# SPACE_v2_2_WEMOS_D1R2.net
KiCad netlist of a schematic drawn in EAGLE
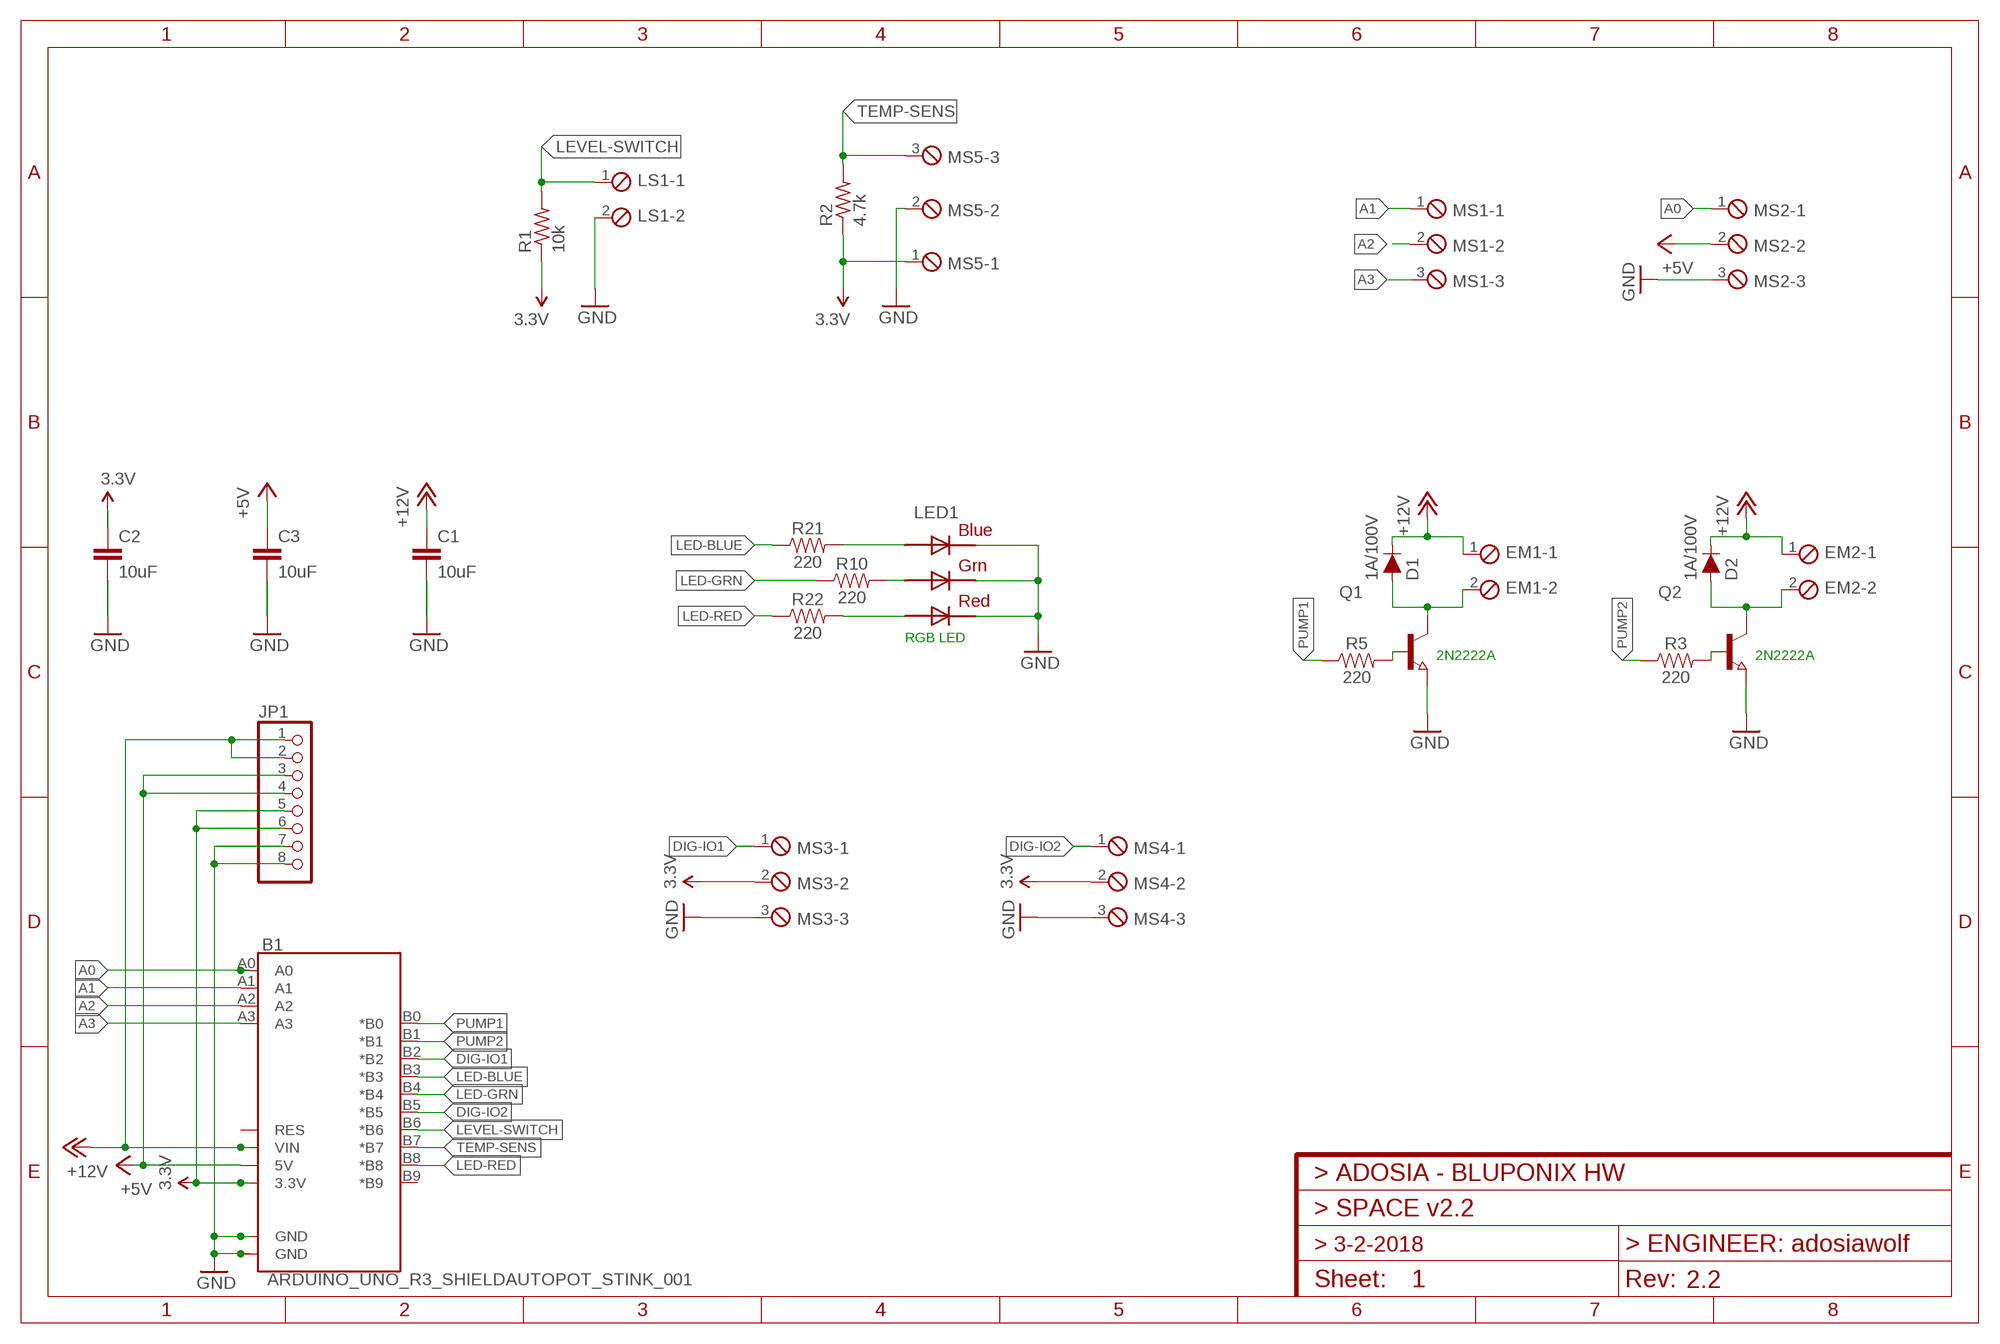
[diagram p0: schematic, sheet 1]

(export (version "E")
  (design (tool "Eeschema 10.0.6"))
  (components
    (comp (ref "B1")
      (value "ARDUINO_UNO_R3_SHIELDAUTOPOT_STINK_001")
      (footprint "eagle-import:UNO_R3_SHIELD_LOCK")
      (libsource (lib "eagle-import") (part "ARDUINO_UNO_R3_SHIELDAUTOPOT_STINK_001"))
    )
    (comp (ref "C1")
      (value "10uF")
      (footprint "eagle-import:0603-CAP@1")
      (libsource (lib "eagle-import") (part "10UF-6.3V-20%(0603)"))
    )
    (comp (ref "C2")
      (value "10uF")
      (footprint "eagle-import:0603-CAP@1")
      (libsource (lib "eagle-import") (part "10UF-6.3V-20%(0603)"))
    )
    (comp (ref "C3")
      (value "10uF")
      (footprint "eagle-import:0603-CAP@1")
      (libsource (lib "eagle-import") (part "10UF-6.3V-20%(0603)"))
    )
    (comp (ref "D1")
      (value "1A/100V")
      (footprint "eagle-import:SOD-323")
      (libsource (lib "eagle-import") (part "DIODE-BAS16J"))
    )
    (comp (ref "D2")
      (value "1A/100V")
      (footprint "eagle-import:SOD-323")
      (libsource (lib "eagle-import") (part "DIODE-BAS16J"))
    )
    (comp (ref "EM1")
      (value "MPT2")
      (footprint "eagle-import:2POL254")
      (libsource (lib "eagle-import") (part "MPT2"))
    )
    (comp (ref "EM2")
      (value "MPT2")
      (footprint "eagle-import:2POL254")
      (libsource (lib "eagle-import") (part "MPT2"))
    )
    (comp (ref "JP1")
      (value "PINHD-1X8/90")
      (footprint "eagle-import:1X08_90")
      (libsource (lib "eagle-import") (part "PINHD-1X8/90"))
    )
    (comp (ref "LED1")
      (value "RGBLED5050")
      (footprint "eagle-import:RGBLED5050")
      (libsource (lib "eagle-import") (part "RGBLED5050"))
    )
    (comp (ref "LS1")
      (value "MPT2")
      (footprint "eagle-import:2POL254")
      (libsource (lib "eagle-import") (part "MPT2"))
    )
    (comp (ref "MS1")
      (value "MPT3")
      (footprint "eagle-import:3POL254")
      (libsource (lib "eagle-import") (part "MPT3"))
    )
    (comp (ref "MS2")
      (value "MPT3")
      (footprint "eagle-import:3POL254")
      (libsource (lib "eagle-import") (part "MPT3"))
    )
    (comp (ref "MS3")
      (value "MPT3")
      (footprint "eagle-import:3POL254")
      (libsource (lib "eagle-import") (part "MPT3"))
    )
    (comp (ref "MS4")
      (value "MPT3")
      (footprint "eagle-import:3POL254")
      (libsource (lib "eagle-import") (part "MPT3"))
    )
    (comp (ref "MS5")
      (value "MPT3")
      (footprint "eagle-import:3POL254")
      (libsource (lib "eagle-import") (part "MPT3"))
    )
    (comp (ref "Q1")
      (value "NPN-TRANSISTOR_SOT23")
      (footprint "eagle-import:SOT23")
      (libsource (lib "eagle-import") (part "NPN-TRANSISTOR_SOT23"))
    )
    (comp (ref "Q2")
      (value "NPN-TRANSISTOR_SOT23")
      (footprint "eagle-import:SOT23")
      (libsource (lib "eagle-import") (part "NPN-TRANSISTOR_SOT23"))
    )
    (comp (ref "R1")
      (value "10k")
      (footprint "eagle-import:M1206")
      (libsource (lib "eagle-import") (part "R-US_M1206"))
    )
    (comp (ref "R2")
      (value "4.7k")
      (footprint "eagle-import:M1206")
      (libsource (lib "eagle-import") (part "R-US_M1206"))
    )
    (comp (ref "R3")
      (value "220")
      (footprint "eagle-import:0603")
      (libsource (lib "eagle-import") (part "220OHM-0603-1/10W-1%"))
    )
    (comp (ref "R5")
      (value "220")
      (footprint "eagle-import:0603")
      (libsource (lib "eagle-import") (part "220OHM-0603-1/10W-1%"))
    )
    (comp (ref "R10")
      (value "220")
      (footprint "eagle-import:0603")
      (libsource (lib "eagle-import") (part "220OHM-0603-1/10W-1%"))
    )
    (comp (ref "R21")
      (value "220")
      (footprint "eagle-import:0603")
      (libsource (lib "eagle-import") (part "220OHM-0603-1/10W-1%"))
    )
    (comp (ref "R22")
      (value "220")
      (footprint "eagle-import:0603")
      (libsource (lib "eagle-import") (part "220OHM-0603-1/10W-1%"))
    )
  )
  (nets
    (net (code "1") (name "+5V") (class "Default")
      (node (ref "B1") (pin "5V") (pinfunction "5V_5V") (pintype "bidirectional"))
      (node (ref "C3") (pin "1") (pinfunction "1_1") (pintype "passive"))
      (node (ref "JP1") (pin "3") (pinfunction "3_3") (pintype "passive"))
      (node (ref "JP1") (pin "4") (pinfunction "4_4") (pintype "passive"))
      (node (ref "MS2") (pin "2") (pinfunction "1_2") (pintype "passive"))
    )
    (net (code "2") (name "+12V") (class "Default")
      (node (ref "B1") (pin "VIN") (pinfunction "VIN_VIN") (pintype "bidirectional"))
      (node (ref "C1") (pin "1") (pinfunction "1_1") (pintype "passive"))
      (node (ref "D1") (pin "C") (pinfunction "C_C") (pintype "passive"))
      (node (ref "D2") (pin "C") (pinfunction "C_C") (pintype "passive"))
      (node (ref "EM1") (pin "1") (pinfunction "1_1") (pintype "passive"))
      (node (ref "EM2") (pin "1") (pinfunction "1_1") (pintype "passive"))
      (node (ref "JP1") (pin "1") (pinfunction "1_1") (pintype "passive"))
      (node (ref "JP1") (pin "2") (pinfunction "2_2") (pintype "passive"))
    )
    (net (code "3") (name "3.3V") (class "Default")
      (node (ref "B1") (pin "3.3V") (pinfunction "3.3V_3.3V") (pintype "bidirectional"))
      (node (ref "C2") (pin "1") (pinfunction "1_1") (pintype "passive"))
      (node (ref "JP1") (pin "5") (pinfunction "5_5") (pintype "passive"))
      (node (ref "JP1") (pin "6") (pinfunction "6_6") (pintype "passive"))
      (node (ref "MS3") (pin "2") (pinfunction "1_2") (pintype "passive"))
      (node (ref "MS4") (pin "2") (pinfunction "1_2") (pintype "passive"))
      (node (ref "MS5") (pin "1") (pinfunction "1_1") (pintype "passive"))
      (node (ref "R1") (pin "1") (pinfunction "1_1") (pintype "passive"))
      (node (ref "R2") (pin "1") (pinfunction "1_1") (pintype "passive"))
    )
    (net (code "4") (name "A0") (class "Default")
      (node (ref "B1") (pin "A0") (pinfunction "A0_A0") (pintype "bidirectional"))
      (node (ref "MS2") (pin "1") (pinfunction "1_1") (pintype "passive"))
    )
    (net (code "5") (name "A1") (class "Default")
      (node (ref "B1") (pin "A1") (pinfunction "A1_A1") (pintype "bidirectional"))
      (node (ref "MS1") (pin "1") (pinfunction "1_1") (pintype "passive"))
    )
    (net (code "6") (name "A2") (class "Default")
      (node (ref "B1") (pin "A2") (pinfunction "A2_A2") (pintype "bidirectional"))
      (node (ref "MS1") (pin "2") (pinfunction "1_2") (pintype "passive"))
    )
    (net (code "7") (name "A3") (class "Default")
      (node (ref "B1") (pin "A3") (pinfunction "A3_A3") (pintype "bidirectional"))
      (node (ref "MS1") (pin "3") (pinfunction "1_3") (pintype "passive"))
    )
    (net (code "8") (name "DIG-IO1") (class "Default")
      (node (ref "B1") (pin "B2") (pinfunction "*B2_B2") (pintype "bidirectional"))
      (node (ref "MS3") (pin "1") (pinfunction "1_1") (pintype "passive"))
    )
    (net (code "9") (name "DIG-IO2") (class "Default")
      (node (ref "B1") (pin "B5") (pinfunction "*B5_B5") (pintype "bidirectional"))
      (node (ref "MS4") (pin "1") (pinfunction "1_1") (pintype "passive"))
    )
    (net (code "10") (name "GND") (class "Default")
      (node (ref "B1") (pin "GND@0") (pinfunction "GND_GND@0") (pintype "bidirectional"))
      (node (ref "B1") (pin "GND@1") (pinfunction "GND_GND@1") (pintype "bidirectional"))
      (node (ref "C1") (pin "2") (pinfunction "2_2") (pintype "passive"))
      (node (ref "C2") (pin "2") (pinfunction "2_2") (pintype "passive"))
      (node (ref "C3") (pin "2") (pinfunction "2_2") (pintype "passive"))
      (node (ref "JP1") (pin "7") (pinfunction "7_7") (pintype "passive"))
      (node (ref "JP1") (pin "8") (pinfunction "8_8") (pintype "passive"))
      (node (ref "LED1") (pin "4") (pinfunction "BLUE_C_4") (pintype "bidirectional"))
      (node (ref "LED1") (pin "5") (pinfunction "RED_C_5") (pintype "bidirectional"))
      (node (ref "LED1") (pin "6") (pinfunction "GREEN_C_6") (pintype "bidirectional"))
      (node (ref "LS1") (pin "2") (pinfunction "1_2") (pintype "passive"))
      (node (ref "MS2") (pin "3") (pinfunction "1_3") (pintype "passive"))
      (node (ref "MS3") (pin "3") (pinfunction "1_3") (pintype "passive"))
      (node (ref "MS4") (pin "3") (pinfunction "1_3") (pintype "passive"))
      (node (ref "MS5") (pin "2") (pinfunction "1_2") (pintype "passive"))
      (node (ref "Q1") (pin "2") (pinfunction "E_2") (pintype "passive"))
      (node (ref "Q2") (pin "2") (pinfunction "E_2") (pintype "passive"))
    )
    (net (code "11") (name "LED-BLUE") (class "Default")
      (node (ref "B1") (pin "B3") (pinfunction "*B3_B3") (pintype "bidirectional"))
      (node (ref "R21") (pin "1") (pinfunction "1_1") (pintype "passive"))
    )
    (net (code "12") (name "LED-GRN") (class "Default")
      (node (ref "B1") (pin "B4") (pinfunction "*B4_B4") (pintype "bidirectional"))
      (node (ref "R10") (pin "1") (pinfunction "1_1") (pintype "passive"))
    )
    (net (code "13") (name "LED-RED") (class "Default")
      (node (ref "B1") (pin "B8") (pinfunction "*B8_B8") (pintype "bidirectional"))
      (node (ref "R22") (pin "1") (pinfunction "1_1") (pintype "passive"))
    )
    (net (code "14") (name "LEVEL-SWITCH") (class "Default")
      (node (ref "B1") (pin "B6") (pinfunction "*B6_B6") (pintype "bidirectional"))
      (node (ref "LS1") (pin "1") (pinfunction "1_1") (pintype "passive"))
      (node (ref "R1") (pin "2") (pinfunction "2_2") (pintype "passive"))
    )
    (net (code "15") (name "Net-(EM1B-1)") (class "Default")
      (node (ref "D1") (pin "A") (pinfunction "A_A") (pintype "passive"))
      (node (ref "EM1") (pin "2") (pinfunction "1_2") (pintype "passive"))
      (node (ref "Q1") (pin "3") (pinfunction "C_3") (pintype "passive"))
    )
    (net (code "16") (name "Net-(EM2B-1)") (class "Default")
      (node (ref "D2") (pin "A") (pinfunction "A_A") (pintype "passive"))
      (node (ref "EM2") (pin "2") (pinfunction "1_2") (pintype "passive"))
      (node (ref "Q2") (pin "3") (pinfunction "C_3") (pintype "passive"))
    )
    (net (code "17") (name "Net-(LED1-BLUE_A)") (class "Default")
      (node (ref "LED1") (pin "3") (pinfunction "BLUE_A_3") (pintype "bidirectional"))
      (node (ref "R21") (pin "2") (pinfunction "2_2") (pintype "passive"))
    )
    (net (code "18") (name "Net-(LED1-GREEN_A)") (class "Default")
      (node (ref "LED1") (pin "1") (pinfunction "GREEN_A_1") (pintype "bidirectional"))
      (node (ref "R10") (pin "2") (pinfunction "2_2") (pintype "passive"))
    )
    (net (code "19") (name "Net-(LED1-RED_A)") (class "Default")
      (node (ref "LED1") (pin "2") (pinfunction "RED_A_2") (pintype "bidirectional"))
      (node (ref "R22") (pin "2") (pinfunction "2_2") (pintype "passive"))
    )
    (net (code "20") (name "Net-(Q1-B)") (class "Default")
      (node (ref "Q1") (pin "1") (pinfunction "B_1") (pintype "passive"))
      (node (ref "R5") (pin "2") (pinfunction "2_2") (pintype "passive"))
    )
    (net (code "21") (name "Net-(Q2-B)") (class "Default")
      (node (ref "Q2") (pin "1") (pinfunction "B_1") (pintype "passive"))
      (node (ref "R3") (pin "2") (pinfunction "2_2") (pintype "passive"))
    )
    (net (code "22") (name "PUMP1") (class "Default")
      (node (ref "B1") (pin "B0") (pinfunction "*B0_B0") (pintype "bidirectional"))
      (node (ref "R5") (pin "1") (pinfunction "1_1") (pintype "passive"))
    )
    (net (code "23") (name "PUMP2") (class "Default")
      (node (ref "B1") (pin "B1") (pinfunction "*B1_B1") (pintype "bidirectional"))
      (node (ref "R3") (pin "1") (pinfunction "1_1") (pintype "passive"))
    )
    (net (code "24") (name "TEMP-SENS") (class "Default")
      (node (ref "B1") (pin "B7") (pinfunction "*B7_B7") (pintype "bidirectional"))
      (node (ref "MS5") (pin "3") (pinfunction "1_3") (pintype "passive"))
      (node (ref "R2") (pin "2") (pinfunction "2_2") (pintype "passive"))
    )
    (net (code "25") (name "unconnected-(B1-*B9-PadB9)") (class "Default")
      (node (ref "B1") (pin "B9") (pinfunction "*B9_B9") (pintype "bidirectional"))
    )
    (net (code "26") (name "unconnected-(B1-PadRES)") (class "Default")
      (node (ref "B1") (pin "RES") (pinfunction "RES_RES") (pintype "bidirectional"))
    )
  )
)
